# RGBW_DirectControl_Eagle650.net
KiCad netlist of a schematic drawn in EAGLE
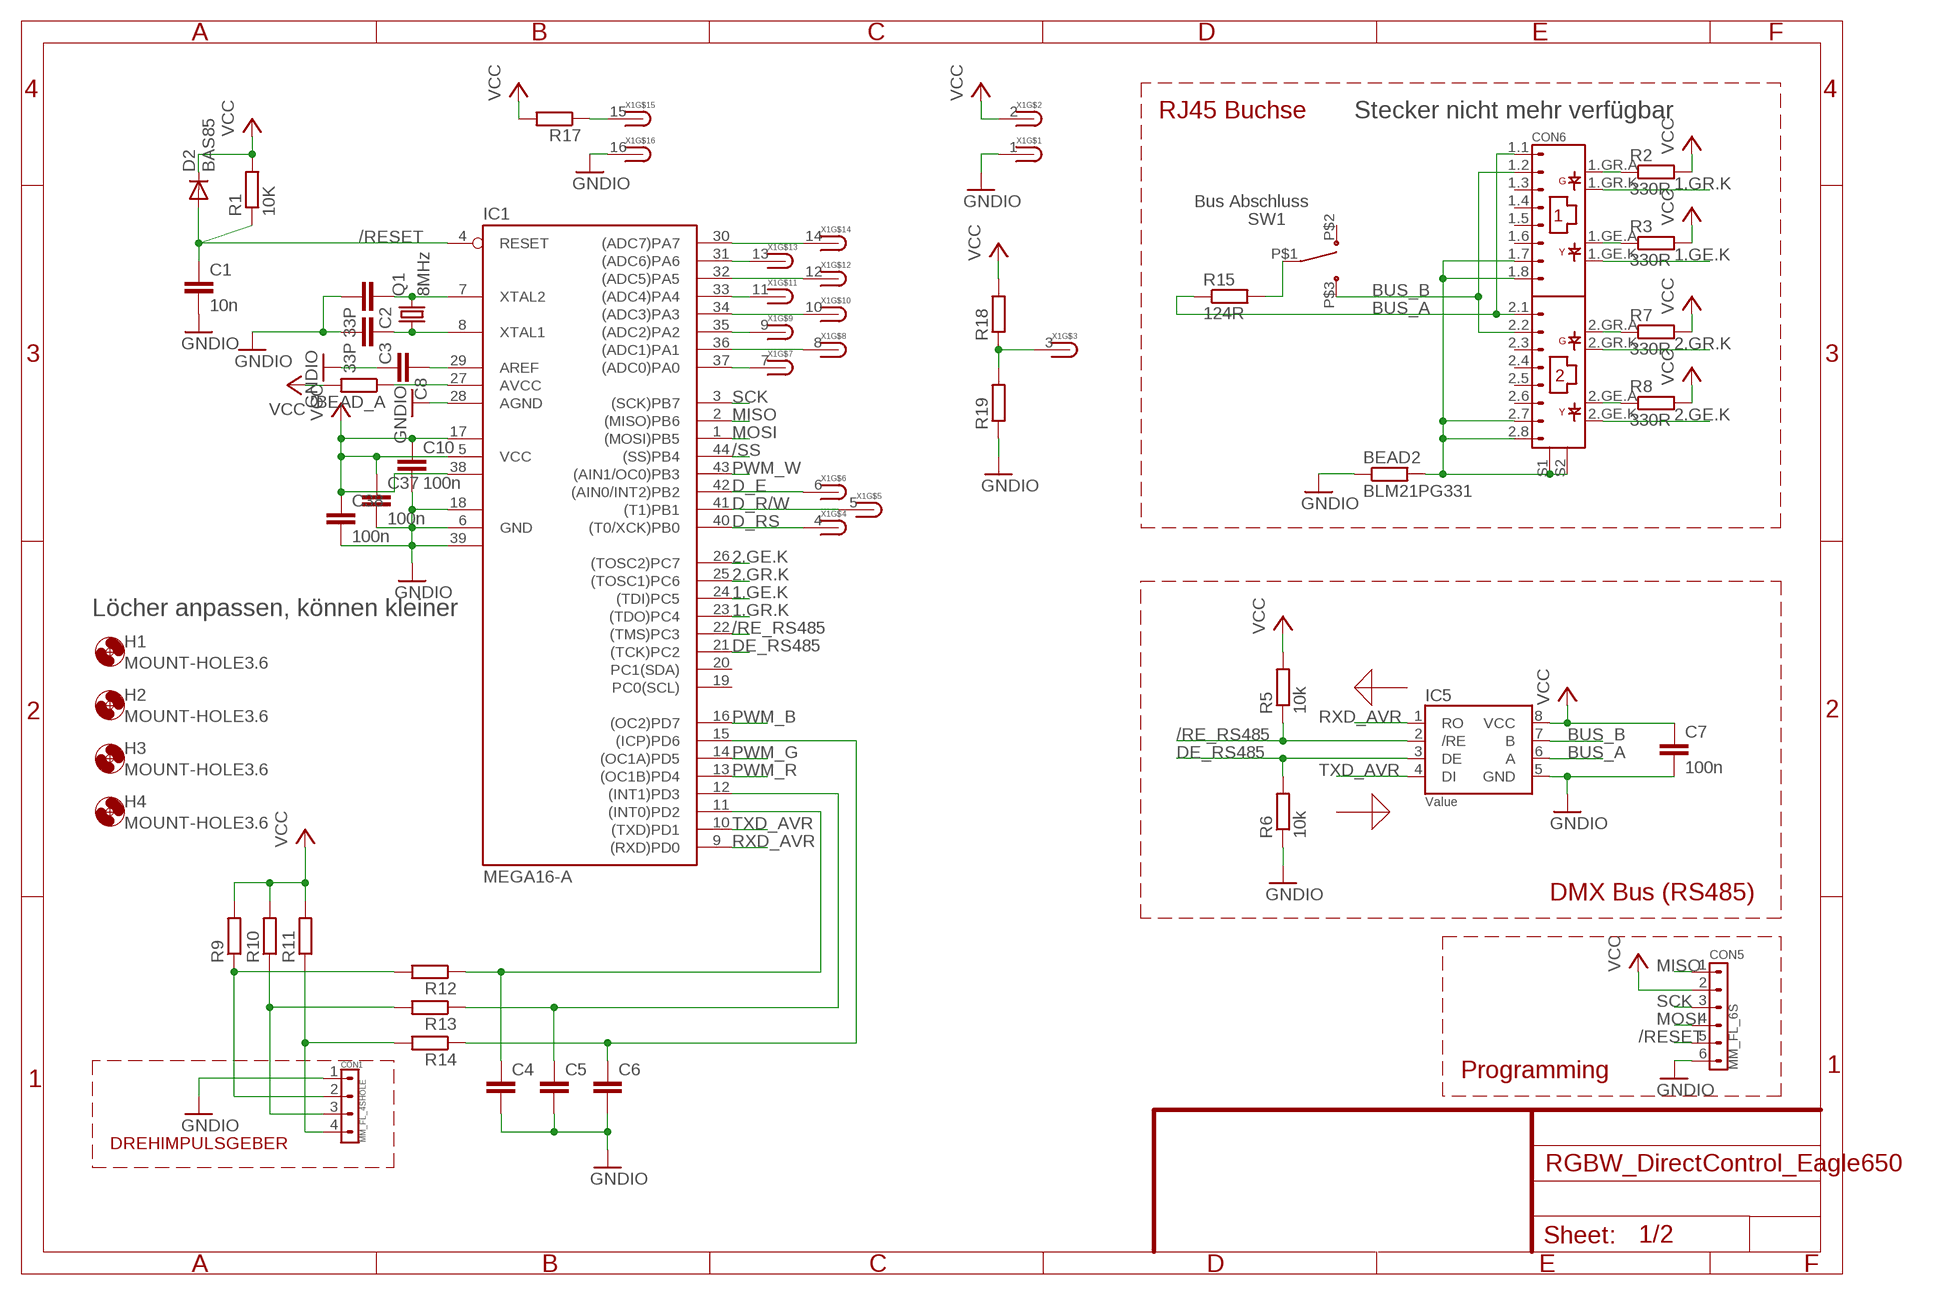
[diagram p0: schematic, sheet 1]
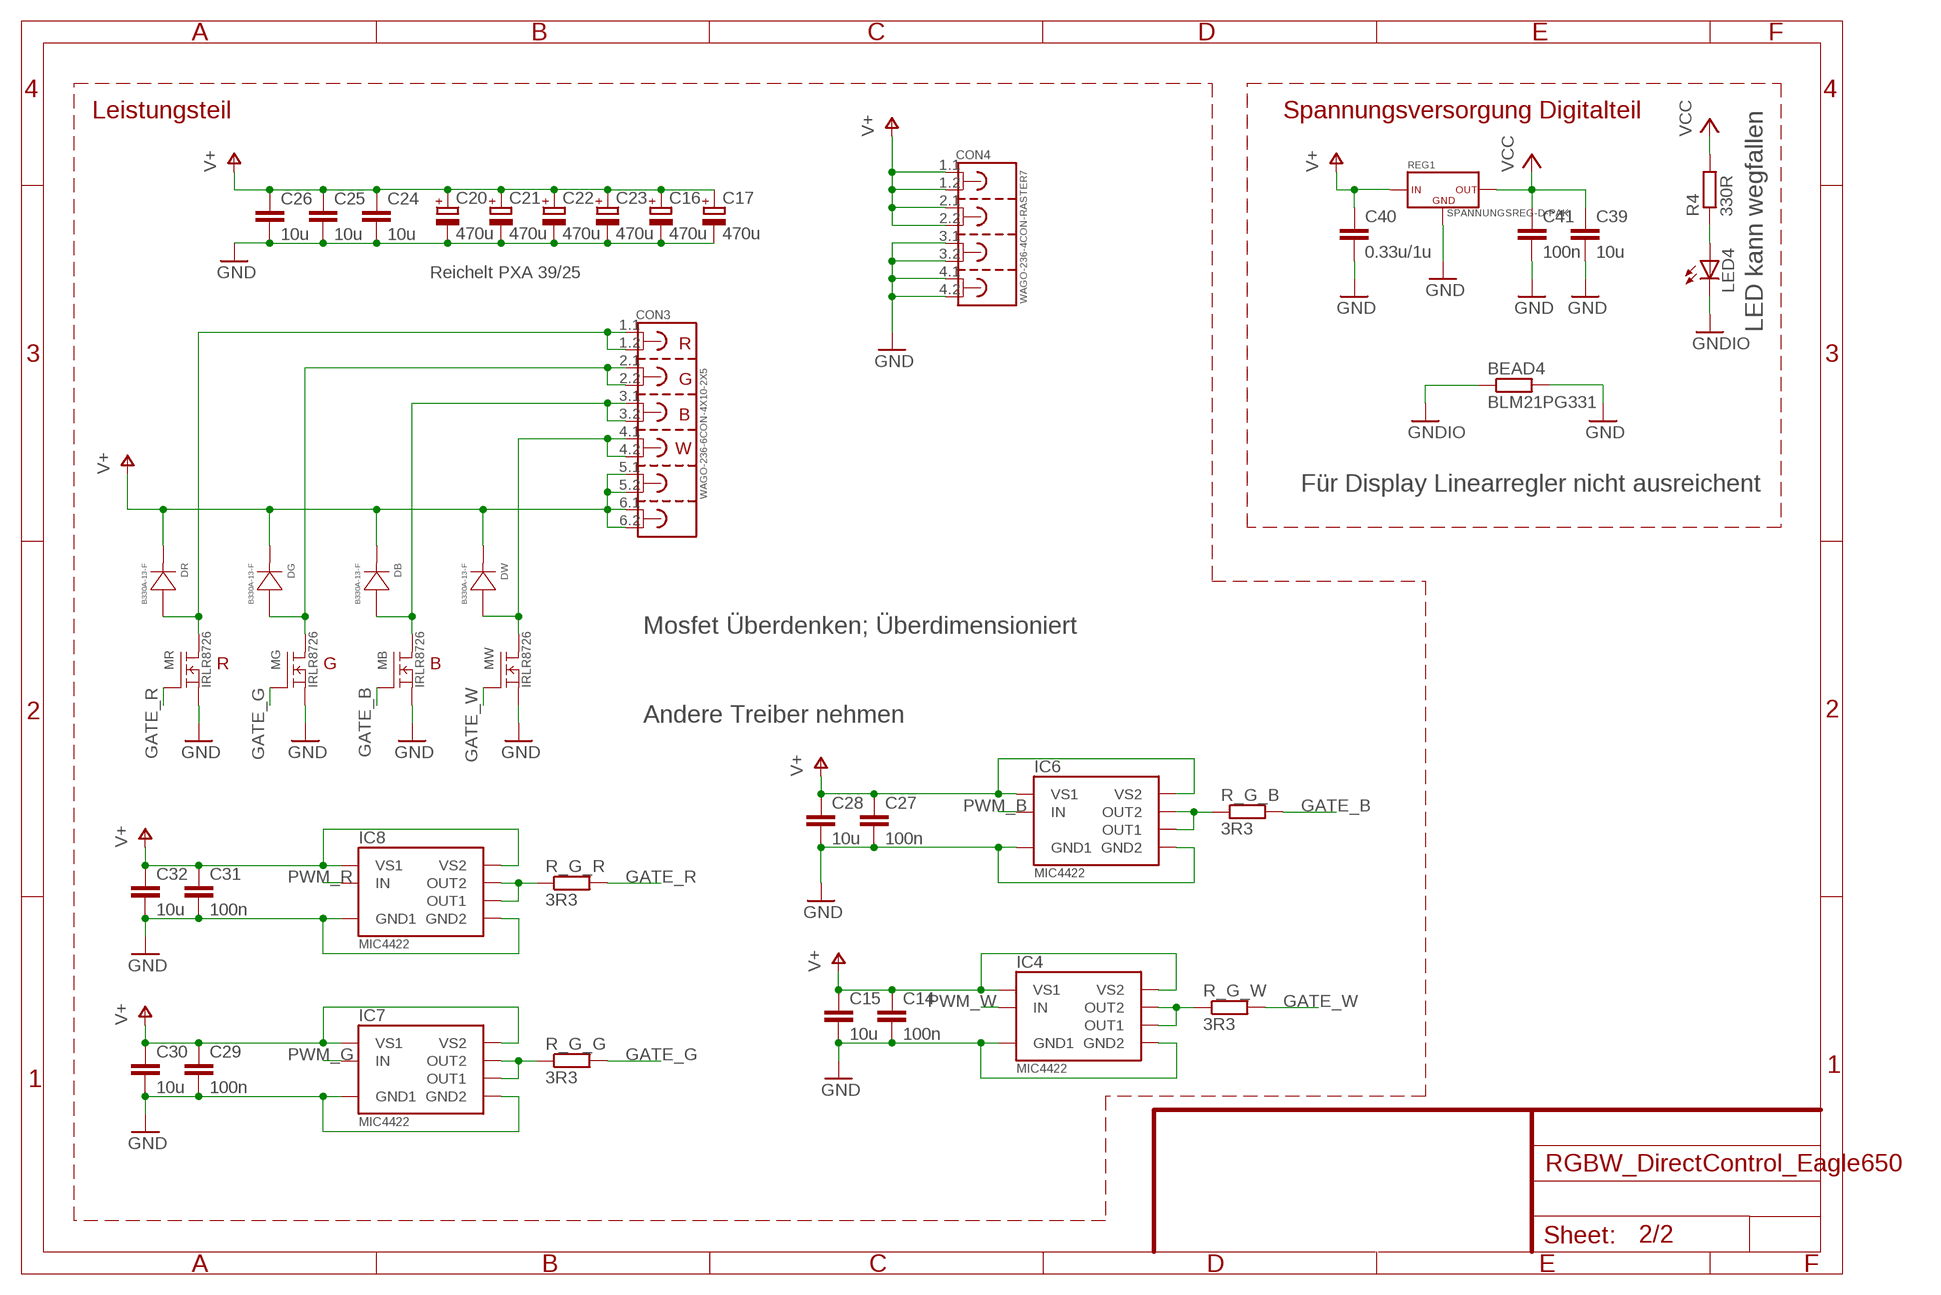
[diagram p1: schematic, sheet 2]

(export (version "E")
  (design (tool "Eeschema 10.0.6"))
  (components
    (comp (ref "BEAD4")
      (value "BLM21PG331")
      (footprint "eagle-import:R0805")
      (libsource (lib "eagle-import") (part "R-EU_R0805"))
    )
    (comp (ref "C14")
      (value "100n")
      (footprint "eagle-import:C0805")
      (libsource (lib "eagle-import") (part "C-EUC0805"))
    )
    (comp (ref "C15")
      (value "10u")
      (footprint "eagle-import:C0805")
      (libsource (lib "eagle-import") (part "C-EUC0805"))
    )
    (comp (ref "C16")
      (value "470u")
      (footprint "eagle-import:E5-10,5")
      (libsource (lib "eagle-import") (part "CPOL-EUE5-10.5"))
    )
    (comp (ref "C17")
      (value "470u")
      (footprint "eagle-import:E5-10,5")
      (libsource (lib "eagle-import") (part "CPOL-EUE5-10.5"))
    )
    (comp (ref "C20")
      (value "470u")
      (footprint "eagle-import:E5-10,5")
      (libsource (lib "eagle-import") (part "CPOL-EUE5-10.5"))
    )
    (comp (ref "C21")
      (value "470u")
      (footprint "eagle-import:E5-10,5")
      (libsource (lib "eagle-import") (part "CPOL-EUE5-10.5"))
    )
    (comp (ref "C22")
      (value "470u")
      (footprint "eagle-import:E5-10,5")
      (libsource (lib "eagle-import") (part "CPOL-EUE5-10.5"))
    )
    (comp (ref "C23")
      (value "470u")
      (footprint "eagle-import:E5-10,5")
      (libsource (lib "eagle-import") (part "CPOL-EUE5-10.5"))
    )
    (comp (ref "C24")
      (value "10u")
      (footprint "eagle-import:C0805")
      (libsource (lib "eagle-import") (part "C-EUC0805"))
    )
    (comp (ref "C25")
      (value "10u")
      (footprint "eagle-import:C0805")
      (libsource (lib "eagle-import") (part "C-EUC0805"))
    )
    (comp (ref "C26")
      (value "10u")
      (footprint "eagle-import:C0805")
      (libsource (lib "eagle-import") (part "C-EUC0805"))
    )
    (comp (ref "C27")
      (value "100n")
      (footprint "eagle-import:C0805")
      (libsource (lib "eagle-import") (part "C-EUC0805"))
    )
    (comp (ref "C28")
      (value "10u")
      (footprint "eagle-import:C0805")
      (libsource (lib "eagle-import") (part "C-EUC0805"))
    )
    (comp (ref "C29")
      (value "100n")
      (footprint "eagle-import:C0805")
      (libsource (lib "eagle-import") (part "C-EUC0805"))
    )
    (comp (ref "C30")
      (value "10u")
      (footprint "eagle-import:C0805")
      (libsource (lib "eagle-import") (part "C-EUC0805"))
    )
    (comp (ref "C31")
      (value "100n")
      (footprint "eagle-import:C0805")
      (libsource (lib "eagle-import") (part "C-EUC0805"))
    )
    (comp (ref "C32")
      (value "10u")
      (footprint "eagle-import:C0805")
      (libsource (lib "eagle-import") (part "C-EUC0805"))
    )
    (comp (ref "C39")
      (value "10u")
      (footprint "eagle-import:C0805")
      (libsource (lib "eagle-import") (part "C-EUC0805"))
    )
    (comp (ref "C40")
      (value "0.33u/1u")
      (footprint "eagle-import:C0805")
      (libsource (lib "eagle-import") (part "C-EUC0805"))
    )
    (comp (ref "C41")
      (value "100n")
      (footprint "eagle-import:C0805")
      (libsource (lib "eagle-import") (part "C-EUC0805"))
    )
    (comp (ref "CON3")
      (value "WAGO-236-6CON-4X10-2X5")
      (footprint "eagle-import:WAGO236_2X5_4X10")
      (libsource (lib "eagle-import") (part "WAGO-236-6CON-4X10-2X5"))
    )
    (comp (ref "CON4")
      (value "WAGO-236-4CON-RASTER7")
      (footprint "eagle-import:WAGO236_7.5_4")
      (libsource (lib "eagle-import") (part "WAGO-236-4CON-RASTER7"))
    )
    (comp (ref "DB")
      (value "B330A-13-F")
      (footprint "eagle-import:SMA")
      (libsource (lib "eagle-import") (part "B330A-13-F"))
    )
    (comp (ref "DG")
      (value "B330A-13-F")
      (footprint "eagle-import:SMA")
      (libsource (lib "eagle-import") (part "B330A-13-F"))
    )
    (comp (ref "DR")
      (value "B330A-13-F")
      (footprint "eagle-import:SMA")
      (libsource (lib "eagle-import") (part "B330A-13-F"))
    )
    (comp (ref "DW")
      (value "B330A-13-F")
      (footprint "eagle-import:SMA")
      (libsource (lib "eagle-import") (part "B330A-13-F"))
    )
    (comp (ref "IC4")
      (value "MIC4422")
      (footprint "eagle-import:SO08")
      (libsource (lib "eagle-import") (part "MIC4422"))
    )
    (comp (ref "IC6")
      (value "MIC4422")
      (footprint "eagle-import:SO08")
      (libsource (lib "eagle-import") (part "MIC4422"))
    )
    (comp (ref "IC7")
      (value "MIC4422")
      (footprint "eagle-import:SO08")
      (libsource (lib "eagle-import") (part "MIC4422"))
    )
    (comp (ref "IC8")
      (value "MIC4422")
      (footprint "eagle-import:SO08")
      (libsource (lib "eagle-import") (part "MIC4422"))
    )
    (comp (ref "LED4")
      (value "LEDCHIP-LED0805")
      (footprint "eagle-import:CHIP-LED0805")
      (libsource (lib "eagle-import") (part "LEDCHIP-LED0805"))
    )
    (comp (ref "MB")
      (value "IRLR8726")
      (footprint "eagle-import:D-PAK")
      (libsource (lib "eagle-import") (part "IRLR8726"))
    )
    (comp (ref "MG")
      (value "IRLR8726")
      (footprint "eagle-import:D-PAK")
      (libsource (lib "eagle-import") (part "IRLR8726"))
    )
    (comp (ref "MR")
      (value "IRLR8726")
      (footprint "eagle-import:D-PAK")
      (libsource (lib "eagle-import") (part "IRLR8726"))
    )
    (comp (ref "MW")
      (value "IRLR8726")
      (footprint "eagle-import:D-PAK")
      (libsource (lib "eagle-import") (part "IRLR8726"))
    )
    (comp (ref "R4")
      (value "330R")
      (footprint "eagle-import:R0805")
      (libsource (lib "eagle-import") (part "R-EU_R0805"))
    )
    (comp (ref "REG1")
      (value "SPANNUNGSREG-D-PAK")
      (footprint "eagle-import:D-PAK")
      (libsource (lib "eagle-import") (part "SPANNUNGSREG-D-PAK"))
    )
    (comp (ref "R_G_B")
      (value "3R3")
      (footprint "eagle-import:R0805")
      (libsource (lib "eagle-import") (part "R-EU_R0805"))
    )
    (comp (ref "R_G_G")
      (value "3R3")
      (footprint "eagle-import:R0805")
      (libsource (lib "eagle-import") (part "R-EU_R0805"))
    )
    (comp (ref "R_G_R")
      (value "3R3")
      (footprint "eagle-import:R0805")
      (libsource (lib "eagle-import") (part "R-EU_R0805"))
    )
    (comp (ref "R_G_W")
      (value "3R3")
      (footprint "eagle-import:R0805")
      (libsource (lib "eagle-import") (part "R-EU_R0805"))
    )
    (comp (ref "BEAD2")
      (value "BLM21PG331")
      (footprint "eagle-import:R0805")
      (libsource (lib "eagle-import") (part "R-EU_R0805"))
    )
    (comp (ref "BEAD_A")
      (value "R-EU_R0805")
      (footprint "eagle-import:R0805")
      (libsource (lib "eagle-import") (part "R-EU_R0805"))
    )
    (comp (ref "C1")
      (value "10n")
      (footprint "eagle-import:C0805")
      (libsource (lib "eagle-import") (part "C-EUC0805"))
    )
    (comp (ref "C2")
      (value "33P")
      (footprint "eagle-import:C0805")
      (libsource (lib "eagle-import") (part "C-EUC0805"))
    )
    (comp (ref "C3")
      (value "33P")
      (footprint "eagle-import:C0805")
      (libsource (lib "eagle-import") (part "C-EUC0805"))
    )
    (comp (ref "C4")
      (value "C-EUC0805")
      (footprint "eagle-import:C0805")
      (libsource (lib "eagle-import") (part "C-EUC0805"))
    )
    (comp (ref "C5")
      (value "C-EUC0805")
      (footprint "eagle-import:C0805")
      (libsource (lib "eagle-import") (part "C-EUC0805"))
    )
    (comp (ref "C6")
      (value "C-EUC0805")
      (footprint "eagle-import:C0805")
      (libsource (lib "eagle-import") (part "C-EUC0805"))
    )
    (comp (ref "C7")
      (value "100n")
      (footprint "eagle-import:C0805")
      (libsource (lib "eagle-import") (part "C-EUC0805"))
    )
    (comp (ref "C8")
      (value "C-EUC0805")
      (footprint "eagle-import:C0805")
      (libsource (lib "eagle-import") (part "C-EUC0805"))
    )
    (comp (ref "C10")
      (value "100n")
      (footprint "eagle-import:C0805")
      (libsource (lib "eagle-import") (part "C-EUC0805"))
    )
    (comp (ref "C37")
      (value "100n")
      (footprint "eagle-import:C0805")
      (libsource (lib "eagle-import") (part "C-EUC0805"))
    )
    (comp (ref "C38")
      (value "100n")
      (footprint "eagle-import:C0805")
      (libsource (lib "eagle-import") (part "C-EUC0805"))
    )
    (comp (ref "CON1")
      (value "MM_FL_4SHOLE")
      (footprint "eagle-import:MM_FL_4G")
      (libsource (lib "eagle-import") (part "MM_FL_4SHOLE"))
    )
    (comp (ref "CON5")
      (value "MM_FL_6S")
      (footprint "eagle-import:MM_FL_6G")
      (libsource (lib "eagle-import") (part "MM_FL_6STH"))
    )
    (comp (ref "CON6")
      (value "RJ45_2ER_LED")
      (footprint "eagle-import:RJ45_2ER_LED")
      (libsource (lib "eagle-import") (part "RJ45_2ER_LED"))
    )
    (comp (ref "D2")
      (value "BAS85")
      (footprint "eagle-import:SOD80C")
      (libsource (lib "eagle-import") (part "DIODE-SOD80C"))
    )
    (comp (ref "H1")
      (value "MOUNT-HOLE3.6")
      (footprint "eagle-import:3,6")
      (libsource (lib "eagle-import") (part "MOUNT-HOLE3.6"))
    )
    (comp (ref "H2")
      (value "MOUNT-HOLE3.6")
      (footprint "eagle-import:3,6")
      (libsource (lib "eagle-import") (part "MOUNT-HOLE3.6"))
    )
    (comp (ref "H3")
      (value "MOUNT-HOLE3.6")
      (footprint "eagle-import:3,6")
      (libsource (lib "eagle-import") (part "MOUNT-HOLE3.6"))
    )
    (comp (ref "H4")
      (value "MOUNT-HOLE3.6")
      (footprint "eagle-import:3,6")
      (libsource (lib "eagle-import") (part "MOUNT-HOLE3.6"))
    )
    (comp (ref "IC1")
      (value "MEGA16-A")
      (footprint "eagle-import:TQFP44")
      (libsource (lib "eagle-import") (part "MEGA16-A"))
    )
    (comp (ref "IC5")
      (value "LT1785")
      (footprint "eagle-import:SO08")
      (libsource (lib "eagle-import") (part "LT1785"))
    )
    (comp (ref "Q1")
      (value "8MHz")
      (footprint "eagle-import:HC49_S")
      (libsource (lib "eagle-import") (part "CRYTALHC49S"))
    )
    (comp (ref "R1")
      (value "10K")
      (footprint "eagle-import:R0805")
      (libsource (lib "eagle-import") (part "R-EU_R0805"))
    )
    (comp (ref "R2")
      (value "330R")
      (footprint "eagle-import:R0805")
      (libsource (lib "eagle-import") (part "R-EU_R0805"))
    )
    (comp (ref "R3")
      (value "330R")
      (footprint "eagle-import:R0805")
      (libsource (lib "eagle-import") (part "R-EU_R0805"))
    )
    (comp (ref "R5")
      (value "10k")
      (footprint "eagle-import:R0805")
      (libsource (lib "eagle-import") (part "R-EU_R0805"))
    )
    (comp (ref "R6")
      (value "10k")
      (footprint "eagle-import:R0805")
      (libsource (lib "eagle-import") (part "R-EU_R0805"))
    )
    (comp (ref "R7")
      (value "330R")
      (footprint "eagle-import:R0805")
      (libsource (lib "eagle-import") (part "R-EU_R0805"))
    )
    (comp (ref "R8")
      (value "330R")
      (footprint "eagle-import:R0805")
      (libsource (lib "eagle-import") (part "R-EU_R0805"))
    )
    (comp (ref "R9")
      (value "R-EU_R0603")
      (footprint "eagle-import:R0603")
      (libsource (lib "eagle-import") (part "R-EU_R0603"))
    )
    (comp (ref "R10")
      (value "R-EU_R0603")
      (footprint "eagle-import:R0603")
      (libsource (lib "eagle-import") (part "R-EU_R0603"))
    )
    (comp (ref "R11")
      (value "R-EU_R0603")
      (footprint "eagle-import:R0603")
      (libsource (lib "eagle-import") (part "R-EU_R0603"))
    )
    (comp (ref "R12")
      (value "R-EU_R0603")
      (footprint "eagle-import:R0603")
      (libsource (lib "eagle-import") (part "R-EU_R0603"))
    )
    (comp (ref "R13")
      (value "R-EU_R0603")
      (footprint "eagle-import:R0603")
      (libsource (lib "eagle-import") (part "R-EU_R0603"))
    )
    (comp (ref "R14")
      (value "R-EU_R0603")
      (footprint "eagle-import:R0603")
      (libsource (lib "eagle-import") (part "R-EU_R0603"))
    )
    (comp (ref "R15")
      (value "124R")
      (footprint "eagle-import:R0805")
      (libsource (lib "eagle-import") (part "R-EU_R0805"))
    )
    (comp (ref "R17")
      (value "R-EU_R0805")
      (footprint "eagle-import:R0805")
      (libsource (lib "eagle-import") (part "R-EU_R0805"))
    )
    (comp (ref "R18")
      (value "R-EU_R0603")
      (footprint "eagle-import:R0603")
      (libsource (lib "eagle-import") (part "R-EU_R0603"))
    )
    (comp (ref "R19")
      (value "R-EU_R0603")
      (footprint "eagle-import:R0603")
      (libsource (lib "eagle-import") (part "R-EU_R0603"))
    )
    (comp (ref "SW1")
      (value "SWITCH_NK236")
      (footprint "eagle-import:SWITCH_NK236")
      (libsource (lib "eagle-import") (part "SWITCH_NK236"))
    )
    (comp (ref "X1")
      (value "MM_FL_16GTH")
      (footprint "eagle-import:MM_FL16G")
      (libsource (lib "eagle-import") (part "MM_FL_16GTH"))
    )
  )
  (nets
    (net (code "1") (name "1.GE.K") (class "Default")
      (node (ref "CON6") (pin "1.GE.K") (pinfunction "1.GE.K_1.GE.K") (pintype "bidirectional"))
      (node (ref "IC1") (pin "24") (pinfunction "(TDI)PC5_24") (pintype "bidirectional"))
    )
    (net (code "2") (name "1.GR.K") (class "Default")
      (node (ref "CON6") (pin "1.GR.K") (pinfunction "1.GR.K_1.GR.K") (pintype "bidirectional"))
      (node (ref "IC1") (pin "23") (pinfunction "(TDO)PC4_23") (pintype "bidirectional"))
    )
    (net (code "3") (name "2.GE.K") (class "Default")
      (node (ref "CON6") (pin "2.GE.K") (pinfunction "2.GE.K_2.GE.K") (pintype "bidirectional"))
      (node (ref "IC1") (pin "26") (pinfunction "(TOSC2)PC7_26") (pintype "bidirectional"))
    )
    (net (code "4") (name "2.GR.K") (class "Default")
      (node (ref "CON6") (pin "2.GR.K") (pinfunction "2.GR.K_2.GR.K") (pintype "bidirectional"))
      (node (ref "IC1") (pin "25") (pinfunction "(TOSC1)PC6_25") (pintype "bidirectional"))
    )
    (net (code "5") (name "BUS_A") (class "Default")
      (node (ref "CON6") (pin "1.1") (pinfunction "1.1_1.1") (pintype "bidirectional"))
      (node (ref "CON6") (pin "2.1") (pinfunction "2.1_2.1") (pintype "bidirectional"))
      (node (ref "IC5") (pin "6") (pinfunction "A_6") (pintype "bidirectional"))
      (node (ref "R15") (pin "1") (pinfunction "1_1") (pintype "passive"))
    )
    (net (code "6") (name "BUS_B") (class "Default")
      (node (ref "CON6") (pin "1.2") (pinfunction "1.2_1.2") (pintype "bidirectional"))
      (node (ref "CON6") (pin "2.2") (pinfunction "2.2_2.2") (pintype "bidirectional"))
      (node (ref "IC5") (pin "7") (pinfunction "B_7") (pintype "bidirectional"))
      (node (ref "SW1") (pin "P$3") (pinfunction "3_P$3") (pintype "bidirectional"))
    )
    (net (code "7") (name "DE_RS485") (class "Default")
      (node (ref "IC1") (pin "21") (pinfunction "(TCK)PC2_21") (pintype "bidirectional"))
      (node (ref "IC5") (pin "3") (pinfunction "DE_3") (pintype "bidirectional"))
      (node (ref "R6") (pin "2") (pinfunction "2_2") (pintype "passive"))
    )
    (net (code "8") (name "D_E") (class "Default")
      (node (ref "IC1") (pin "42") (pinfunction "(AIN0/INT2)PB2_42") (pintype "bidirectional"))
      (node (ref "X1") (pin "6") (pinfunction "P$1_6") (pintype "bidirectional"))
    )
    (net (code "9") (name "D_RS") (class "Default")
      (node (ref "IC1") (pin "40") (pinfunction "(T0/XCK)PB0_40") (pintype "bidirectional"))
      (node (ref "X1") (pin "4") (pinfunction "P$1_4") (pintype "bidirectional"))
    )
    (net (code "10") (name "D_R{slash}W") (class "Default")
      (node (ref "IC1") (pin "41") (pinfunction "(T1)PB1_41") (pintype "bidirectional"))
      (node (ref "X1") (pin "5") (pinfunction "P$1_5") (pintype "bidirectional"))
    )
    (net (code "11") (name "GATE_B") (class "Default")
      (node (ref "MB") (pin "G") (pinfunction "G_G") (pintype "bidirectional"))
      (node (ref "R_G_B") (pin "2") (pinfunction "2_2") (pintype "passive"))
    )
    (net (code "12") (name "GATE_G") (class "Default")
      (node (ref "MG") (pin "G") (pinfunction "G_G") (pintype "bidirectional"))
      (node (ref "R_G_G") (pin "2") (pinfunction "2_2") (pintype "passive"))
    )
    (net (code "13") (name "GATE_R") (class "Default")
      (node (ref "MR") (pin "G") (pinfunction "G_G") (pintype "bidirectional"))
      (node (ref "R_G_R") (pin "2") (pinfunction "2_2") (pintype "passive"))
    )
    (net (code "14") (name "GATE_W") (class "Default")
      (node (ref "MW") (pin "G") (pinfunction "G_G") (pintype "bidirectional"))
      (node (ref "R_G_W") (pin "2") (pinfunction "2_2") (pintype "passive"))
    )
    (net (code "15") (name "GND") (class "Default")
      (node (ref "BEAD4") (pin "2") (pinfunction "2_2") (pintype "passive"))
      (node (ref "C14") (pin "2") (pinfunction "2_2") (pintype "passive"))
      (node (ref "C15") (pin "2") (pinfunction "2_2") (pintype "passive"))
      (node (ref "C16") (pin "-") (pinfunction "-_-") (pintype "passive"))
      (node (ref "C17") (pin "-") (pinfunction "-_-") (pintype "passive"))
      (node (ref "C20") (pin "-") (pinfunction "-_-") (pintype "passive"))
      (node (ref "C21") (pin "-") (pinfunction "-_-") (pintype "passive"))
      (node (ref "C22") (pin "-") (pinfunction "-_-") (pintype "passive"))
      (node (ref "C23") (pin "-") (pinfunction "-_-") (pintype "passive"))
      (node (ref "C24") (pin "2") (pinfunction "2_2") (pintype "passive"))
      (node (ref "C25") (pin "2") (pinfunction "2_2") (pintype "passive"))
      (node (ref "C26") (pin "2") (pinfunction "2_2") (pintype "passive"))
      (node (ref "C27") (pin "2") (pinfunction "2_2") (pintype "passive"))
      (node (ref "C28") (pin "2") (pinfunction "2_2") (pintype "passive"))
      (node (ref "C29") (pin "2") (pinfunction "2_2") (pintype "passive"))
      (node (ref "C30") (pin "2") (pinfunction "2_2") (pintype "passive"))
      (node (ref "C31") (pin "2") (pinfunction "2_2") (pintype "passive"))
      (node (ref "C32") (pin "2") (pinfunction "2_2") (pintype "passive"))
      (node (ref "C39") (pin "2") (pinfunction "2_2") (pintype "passive"))
      (node (ref "C40") (pin "2") (pinfunction "2_2") (pintype "passive"))
      (node (ref "C41") (pin "2") (pinfunction "2_2") (pintype "passive"))
      (node (ref "CON4") (pin "3.1") (pinfunction "P$5_3.1") (pintype "bidirectional"))
      (node (ref "CON4") (pin "3.2") (pinfunction "P$6_3.2") (pintype "bidirectional"))
      (node (ref "CON4") (pin "4.1") (pinfunction "P$7_4.1") (pintype "bidirectional"))
      (node (ref "CON4") (pin "4.2") (pinfunction "P$8_4.2") (pintype "bidirectional"))
      (node (ref "IC4") (pin "4") (pinfunction "GND1_4") (pintype "bidirectional"))
      (node (ref "IC4") (pin "5") (pinfunction "GND2_5") (pintype "bidirectional"))
      (node (ref "IC6") (pin "4") (pinfunction "GND1_4") (pintype "bidirectional"))
      (node (ref "IC6") (pin "5") (pinfunction "GND2_5") (pintype "bidirectional"))
      (node (ref "IC7") (pin "4") (pinfunction "GND1_4") (pintype "bidirectional"))
      (node (ref "IC7") (pin "5") (pinfunction "GND2_5") (pintype "bidirectional"))
      (node (ref "IC8") (pin "4") (pinfunction "GND1_4") (pintype "bidirectional"))
      (node (ref "IC8") (pin "5") (pinfunction "GND2_5") (pintype "bidirectional"))
      (node (ref "MB") (pin "S") (pinfunction "S_S") (pintype "bidirectional"))
      (node (ref "MG") (pin "S") (pinfunction "S_S") (pintype "bidirectional"))
      (node (ref "MR") (pin "S") (pinfunction "S_S") (pintype "bidirectional"))
      (node (ref "MW") (pin "S") (pinfunction "S_S") (pintype "bidirectional"))
      (node (ref "REG1") (pin "D") (pinfunction "GND_D") (pintype "bidirectional"))
    )
    (net (code "16") (name "GNDIO") (class "Default")
      (node (ref "BEAD2") (pin "1") (pinfunction "1_1") (pintype "passive"))
      (node (ref "BEAD4") (pin "1") (pinfunction "1_1") (pintype "passive"))
      (node (ref "C1") (pin "2") (pinfunction "2_2") (pintype "passive"))
      (node (ref "C10") (pin "2") (pinfunction "2_2") (pintype "passive"))
      (node (ref "C2") (pin "2") (pinfunction "2_2") (pintype "passive"))
      (node (ref "C3") (pin "2") (pinfunction "2_2") (pintype "passive"))
      (node (ref "C37") (pin "2") (pinfunction "2_2") (pintype "passive"))
      (node (ref "C38") (pin "2") (pinfunction "2_2") (pintype "passive"))
      (node (ref "C4") (pin "2") (pinfunction "2_2") (pintype "passive"))
      (node (ref "C5") (pin "2") (pinfunction "2_2") (pintype "passive"))
      (node (ref "C6") (pin "2") (pinfunction "2_2") (pintype "passive"))
      (node (ref "C7") (pin "2") (pinfunction "2_2") (pintype "passive"))
      (node (ref "C8") (pin "2") (pinfunction "2_2") (pintype "passive"))
      (node (ref "CON1") (pin "1") (pinfunction "P$1_1") (pintype "bidirectional"))
      (node (ref "CON5") (pin "6") (pinfunction "P$6_6") (pintype "bidirectional"))
      (node (ref "IC1") (pin "18") (pinfunction "GND1_18") (pintype "power_in"))
      (node (ref "IC1") (pin "28") (pinfunction "AGND_28") (pintype "power_in"))
      (node (ref "IC1") (pin "39") (pinfunction "GND2_39") (pintype "power_in"))
      (node (ref "IC1") (pin "6") (pinfunction "GND_6") (pintype "power_in"))
      (node (ref "IC5") (pin "5") (pinfunction "GND_5") (pintype "bidirectional"))
      (node (ref "LED4") (pin "C") (pinfunction "C_C") (pintype "passive"))
      (node (ref "R19") (pin "1") (pinfunction "1_1") (pintype "passive"))
      (node (ref "R6") (pin "1") (pinfunction "1_1") (pintype "passive"))
      (node (ref "X1") (pin "1") (pinfunction "P$1_1") (pintype "bidirectional"))
      (node (ref "X1") (pin "16") (pinfunction "P$1_16") (pintype "bidirectional"))
    )
    (net (code "17") (name "MISO") (class "Default")
      (node (ref "CON5") (pin "1") (pinfunction "P$1_1") (pintype "bidirectional"))
      (node (ref "IC1") (pin "2") (pinfunction "(MISO)PB6_2") (pintype "bidirectional"))
    )
    (net (code "18") (name "MOSI") (class "Default")
      (node (ref "CON5") (pin "4") (pinfunction "P$4_4") (pintype "bidirectional"))
      (node (ref "IC1") (pin "1") (pinfunction "(MOSI)PB5_1") (pintype "bidirectional"))
    )
    (net (code "19") (name "Net-(BEAD2-Pad2)") (class "Default")
      (node (ref "BEAD2") (pin "2") (pinfunction "2_2") (pintype "passive"))
      (node (ref "CON6") (pin "1.7") (pinfunction "1.7_1.7") (pintype "bidirectional"))
      (node (ref "CON6") (pin "1.8") (pinfunction "1.8_1.8") (pintype "bidirectional"))
      (node (ref "CON6") (pin "2.7") (pinfunction "2.7_2.7") (pintype "bidirectional"))
      (node (ref "CON6") (pin "2.8") (pinfunction "2.8_2.8") (pintype "bidirectional"))
      (node (ref "CON6") (pin "S1") (pinfunction "S1_S1") (pintype "bidirectional"))
      (node (ref "CON6") (pin "S2") (pinfunction "S2_S2") (pintype "bidirectional"))
    )
    (net (code "20") (name "Net-(CON1-P$2)") (class "Default")
      (node (ref "CON1") (pin "2") (pinfunction "P$2_2") (pintype "bidirectional"))
      (node (ref "R12") (pin "2") (pinfunction "2_2") (pintype "passive"))
      (node (ref "R9") (pin "1") (pinfunction "1_1") (pintype "passive"))
    )
    (net (code "21") (name "Net-(CON1-P$3)") (class "Default")
      (node (ref "CON1") (pin "3") (pinfunction "P$3_3") (pintype "bidirectional"))
      (node (ref "R10") (pin "1") (pinfunction "1_1") (pintype "passive"))
      (node (ref "R13") (pin "2") (pinfunction "2_2") (pintype "passive"))
    )
    (net (code "22") (name "Net-(CON1-P$4)") (class "Default")
      (node (ref "CON1") (pin "4") (pinfunction "P$4_4") (pintype "bidirectional"))
      (node (ref "R11") (pin "1") (pinfunction "1_1") (pintype "passive"))
      (node (ref "R14") (pin "2") (pinfunction "2_2") (pintype "passive"))
    )
    (net (code "23") (name "Net-(CON3-3.3)") (class "Default")
      (node (ref "CON3") (pin "3.1") (pinfunction "3.1_3.1") (pintype "bidirectional"))
      (node (ref "CON3") (pin "3.2") (pinfunction "3.3_3.2") (pintype "bidirectional"))
      (node (ref "DB") (pin "A") (pinfunction "A_A") (pintype "bidirectional"))
      (node (ref "MB") (pin "D") (pinfunction "D_D") (pintype "bidirectional"))
    )
    (net (code "24") (name "Net-(CON3-Pad1.1)") (class "Default")
      (node (ref "CON3") (pin "1.1") (pinfunction "1.1_1.1") (pintype "bidirectional"))
      (node (ref "CON3") (pin "1.2") (pinfunction "1.2_1.2") (pintype "bidirectional"))
      (node (ref "DR") (pin "A") (pinfunction "A_A") (pintype "bidirectional"))
      (node (ref "MR") (pin "D") (pinfunction "D_D") (pintype "bidirectional"))
    )
    (net (code "25") (name "Net-(CON3-Pad2.1)") (class "Default")
      (node (ref "CON3") (pin "2.1") (pinfunction "2.1_2.1") (pintype "bidirectional"))
      (node (ref "CON3") (pin "2.2") (pinfunction "2.2_2.2") (pintype "bidirectional"))
      (node (ref "DG") (pin "A") (pinfunction "A_A") (pintype "bidirectional"))
      (node (ref "MG") (pin "D") (pinfunction "D_D") (pintype "bidirectional"))
    )
    (net (code "26") (name "Net-(CON3-Pad4.1)") (class "Default")
      (node (ref "CON3") (pin "4.1") (pinfunction "4.1_4.1") (pintype "bidirectional"))
      (node (ref "CON3") (pin "4.2") (pinfunction "4.2_4.2") (pintype "bidirectional"))
      (node (ref "DW") (pin "A") (pinfunction "A_A") (pintype "bidirectional"))
      (node (ref "MW") (pin "D") (pinfunction "D_D") (pintype "bidirectional"))
    )
    (net (code "27") (name "Net-(CON6-Pad1.GE.A)") (class "Default")
      (node (ref "CON6") (pin "1.GE.A") (pinfunction "1.GE.A_1.GE.A") (pintype "bidirectional"))
      (node (ref "R3") (pin "1") (pinfunction "1_1") (pintype "passive"))
    )
    (net (code "28") (name "Net-(CON6-Pad1.GR.A)") (class "Default")
      (node (ref "CON6") (pin "1.GR.A") (pinfunction "1.GR.A_1.GR.A") (pintype "bidirectional"))
      (node (ref "R2") (pin "1") (pinfunction "1_1") (pintype "passive"))
    )
    (net (code "29") (name "Net-(CON6-Pad2.GE.A)") (class "Default")
      (node (ref "CON6") (pin "2.GE.A") (pinfunction "2.GE.A_2.GE.A") (pintype "bidirectional"))
      (node (ref "R8") (pin "1") (pinfunction "1_1") (pintype "passive"))
    )
    (net (code "30") (name "Net-(CON6-Pad2.GR.A)") (class "Default")
      (node (ref "CON6") (pin "2.GR.A") (pinfunction "2.GR.A_2.GR.A") (pintype "bidirectional"))
      (node (ref "R7") (pin "1") (pinfunction "1_1") (pintype "passive"))
    )
    (net (code "31") (name "Net-(IC1-(ADC0)PA0)") (class "Default")
      (node (ref "IC1") (pin "37") (pinfunction "(ADC0)PA0_37") (pintype "bidirectional"))
      (node (ref "X1") (pin "7") (pinfunction "P$1_7") (pintype "bidirectional"))
    )
    (net (code "32") (name "Net-(IC1-(ADC1)PA1)") (class "Default")
      (node (ref "IC1") (pin "36") (pinfunction "(ADC1)PA1_36") (pintype "bidirectional"))
      (node (ref "X1") (pin "8") (pinfunction "P$1_8") (pintype "bidirectional"))
    )
    (net (code "33") (name "Net-(IC1-(ADC2)PA2)") (class "Default")
      (node (ref "IC1") (pin "35") (pinfunction "(ADC2)PA2_35") (pintype "bidirectional"))
      (node (ref "X1") (pin "9") (pinfunction "P$1_9") (pintype "bidirectional"))
    )
    (net (code "34") (name "Net-(IC1-(ADC3)PA3)") (class "Default")
      (node (ref "IC1") (pin "34") (pinfunction "(ADC3)PA3_34") (pintype "bidirectional"))
      (node (ref "X1") (pin "10") (pinfunction "P$1_10") (pintype "bidirectional"))
    )
    (net (code "35") (name "Net-(IC1-(ADC4)PA4)") (class "Default")
      (node (ref "IC1") (pin "33") (pinfunction "(ADC4)PA4_33") (pintype "bidirectional"))
      (node (ref "X1") (pin "11") (pinfunction "P$1_11") (pintype "bidirectional"))
    )
    (net (code "36") (name "Net-(IC1-(ADC5)PA5)") (class "Default")
      (node (ref "IC1") (pin "32") (pinfunction "(ADC5)PA5_32") (pintype "bidirectional"))
      (node (ref "X1") (pin "12") (pinfunction "P$1_12") (pintype "bidirectional"))
    )
    (net (code "37") (name "Net-(IC1-(ADC6)PA6)") (class "Default")
      (node (ref "IC1") (pin "31") (pinfunction "(ADC6)PA6_31") (pintype "bidirectional"))
      (node (ref "X1") (pin "13") (pinfunction "P$1_13") (pintype "bidirectional"))
    )
    (net (code "38") (name "Net-(IC1-(ADC7)PA7)") (class "Default")
      (node (ref "IC1") (pin "30") (pinfunction "(ADC7)PA7_30") (pintype "bidirectional"))
      (node (ref "X1") (pin "14") (pinfunction "P$1_14") (pintype "bidirectional"))
    )
    (net (code "39") (name "Net-(IC1-(ICP)PD6)") (class "Default")
      (node (ref "C6") (pin "1") (pinfunction "1_1") (pintype "passive"))
      (node (ref "IC1") (pin "15") (pinfunction "(ICP)PD6_15") (pintype "bidirectional"))
      (node (ref "R14") (pin "1") (pinfunction "1_1") (pintype "passive"))
    )
    (net (code "40") (name "Net-(IC1-(INT0)PD2)") (class "Default")
      (node (ref "C4") (pin "1") (pinfunction "1_1") (pintype "passive"))
      (node (ref "IC1") (pin "11") (pinfunction "(INT0)PD2_11") (pintype "bidirectional"))
      (node (ref "R12") (pin "1") (pinfunction "1_1") (pintype "passive"))
    )
    (net (code "41") (name "Net-(IC1-(INT1)PD3)") (class "Default")
      (node (ref "C5") (pin "1") (pinfunction "1_1") (pintype "passive"))
      (node (ref "IC1") (pin "12") (pinfunction "(INT1)PD3_12") (pintype "bidirectional"))
      (node (ref "R13") (pin "1") (pinfunction "1_1") (pintype "passive"))
    )
    (net (code "42") (name "Net-(IC1-AREF)") (class "Default")
      (node (ref "C8") (pin "1") (pinfunction "1_1") (pintype "passive"))
      (node (ref "IC1") (pin "29") (pinfunction "AREF_29") (pintype "power_in"))
    )
    (net (code "43") (name "Net-(IC1-AVCC)") (class "Default")
      (node (ref "BEAD_A") (pin "1") (pinfunction "1_1") (pintype "passive"))
      (node (ref "IC1") (pin "27") (pinfunction "AVCC_27") (pintype "power_in"))
    )
    (net (code "44") (name "Net-(IC1-XTAL1)") (class "Default")
      (node (ref "C3") (pin "1") (pinfunction "1_1") (pintype "passive"))
      (node (ref "IC1") (pin "8") (pinfunction "XTAL1_8") (pintype "bidirectional"))
      (node (ref "Q1") (pin "1") (pinfunction "1_1") (pintype "passive"))
    )
    (net (code "45") (name "Net-(IC1-XTAL2)") (class "Default")
      (node (ref "C2") (pin "1") (pinfunction "1_1") (pintype "passive"))
      (node (ref "IC1") (pin "7") (pinfunction "XTAL2_7") (pintype "bidirectional"))
      (node (ref "Q1") (pin "2") (pinfunction "2_2") (pintype "passive"))
    )
    (net (code "46") (name "Net-(IC4-OUT1)") (class "Default")
      (node (ref "IC4") (pin "6") (pinfunction "OUT1_6") (pintype "bidirectional"))
      (node (ref "IC4") (pin "7") (pinfunction "OUT2_7") (pintype "bidirectional"))
      (node (ref "R_G_W") (pin "1") (pinfunction "1_1") (pintype "passive"))
    )
    (net (code "47") (name "Net-(IC6-OUT1)") (class "Default")
      (node (ref "IC6") (pin "6") (pinfunction "OUT1_6") (pintype "bidirectional"))
      (node (ref "IC6") (pin "7") (pinfunction "OUT2_7") (pintype "bidirectional"))
      (node (ref "R_G_B") (pin "1") (pinfunction "1_1") (pintype "passive"))
    )
    (net (code "48") (name "Net-(IC7-OUT1)") (class "Default")
      (node (ref "IC7") (pin "6") (pinfunction "OUT1_6") (pintype "bidirectional"))
      (node (ref "IC7") (pin "7") (pinfunction "OUT2_7") (pintype "bidirectional"))
      (node (ref "R_G_G") (pin "1") (pinfunction "1_1") (pintype "passive"))
    )
    (net (code "49") (name "Net-(IC8-OUT1)") (class "Default")
      (node (ref "IC8") (pin "6") (pinfunction "OUT1_6") (pintype "bidirectional"))
      (node (ref "IC8") (pin "7") (pinfunction "OUT2_7") (pintype "bidirectional"))
      (node (ref "R_G_R") (pin "1") (pinfunction "1_1") (pintype "passive"))
    )
    (net (code "50") (name "Net-(LED4-PadA)") (class "Default")
      (node (ref "LED4") (pin "A") (pinfunction "A_A") (pintype "passive"))
      (node (ref "R4") (pin "1") (pinfunction "1_1") (pintype "passive"))
    )
    (net (code "51") (name "Net-(SW1-1)") (class "Default")
      (node (ref "R15") (pin "2") (pinfunction "2_2") (pintype "passive"))
      (node (ref "SW1") (pin "P$1") (pinfunction "1_P$1") (pintype "bidirectional"))
    )
    (net (code "52") (name "Net-(X1G-P$1)") (class "Default")
      (node (ref "R17") (pin "1") (pinfunction "1_1") (pintype "passive"))
      (node (ref "X1") (pin "15") (pinfunction "P$1_15") (pintype "bidirectional"))
    )
    (net (code "53") (name "Net-(X1J-P$1)") (class "Default")
      (node (ref "R18") (pin "1") (pinfunction "1_1") (pintype "passive"))
      (node (ref "R19") (pin "2") (pinfunction "2_2") (pintype "passive"))
      (node (ref "X1") (pin "3") (pinfunction "P$1_3") (pintype "bidirectional"))
    )
    (net (code "54") (name "PWM_B") (class "Default")
      (node (ref "IC1") (pin "16") (pinfunction "(OC2)PD7_16") (pintype "bidirectional"))
      (node (ref "IC6") (pin "2") (pinfunction "IN_2") (pintype "bidirectional"))
    )
    (net (code "55") (name "PWM_G") (class "Default")
      (node (ref "IC1") (pin "14") (pinfunction "(OC1A)PD5_14") (pintype "bidirectional"))
      (node (ref "IC7") (pin "2") (pinfunction "IN_2") (pintype "bidirectional"))
    )
    (net (code "56") (name "PWM_R") (class "Default")
      (node (ref "IC1") (pin "13") (pinfunction "(OC1B)PD4_13") (pintype "bidirectional"))
      (node (ref "IC8") (pin "2") (pinfunction "IN_2") (pintype "bidirectional"))
    )
    (net (code "57") (name "PWM_W") (class "Default")
      (node (ref "IC1") (pin "43") (pinfunction "(AIN1/OC0)PB3_43") (pintype "bidirectional"))
      (node (ref "IC4") (pin "2") (pinfunction "IN_2") (pintype "bidirectional"))
    )
    (net (code "58") (name "RXD_AVR") (class "Default")
      (node (ref "IC1") (pin "9") (pinfunction "(RXD)PD0_9") (pintype "bidirectional"))
      (node (ref "IC5") (pin "1") (pinfunction "RO_1") (pintype "bidirectional"))
    )
    (net (code "59") (name "SCK") (class "Default")
      (node (ref "CON5") (pin "3") (pinfunction "P$3_3") (pintype "bidirectional"))
      (node (ref "IC1") (pin "3") (pinfunction "(SCK)PB7_3") (pintype "bidirectional"))
    )
    (net (code "60") (name "TXD_AVR") (class "Default")
      (node (ref "IC1") (pin "10") (pinfunction "(TXD)PD1_10") (pintype "bidirectional"))
      (node (ref "IC5") (pin "4") (pinfunction "DI_4") (pintype "bidirectional"))
    )
    (net (code "61") (name "V+") (class "Default")
      (node (ref "C14") (pin "1") (pinfunction "1_1") (pintype "passive"))
      (node (ref "C15") (pin "1") (pinfunction "1_1") (pintype "passive"))
      (node (ref "C16") (pin "+") (pinfunction "+_+") (pintype "passive"))
      (node (ref "C17") (pin "+") (pinfunction "+_+") (pintype "passive"))
      (node (ref "C20") (pin "+") (pinfunction "+_+") (pintype "passive"))
      (node (ref "C21") (pin "+") (pinfunction "+_+") (pintype "passive"))
      (node (ref "C22") (pin "+") (pinfunction "+_+") (pintype "passive"))
      (node (ref "C23") (pin "+") (pinfunction "+_+") (pintype "passive"))
      (node (ref "C24") (pin "1") (pinfunction "1_1") (pintype "passive"))
      (node (ref "C25") (pin "1") (pinfunction "1_1") (pintype "passive"))
      (node (ref "C26") (pin "1") (pinfunction "1_1") (pintype "passive"))
      (node (ref "C27") (pin "1") (pinfunction "1_1") (pintype "passive"))
      (node (ref "C28") (pin "1") (pinfunction "1_1") (pintype "passive"))
      (node (ref "C29") (pin "1") (pinfunction "1_1") (pintype "passive"))
      (node (ref "C30") (pin "1") (pinfunction "1_1") (pintype "passive"))
      (node (ref "C31") (pin "1") (pinfunction "1_1") (pintype "passive"))
      (node (ref "C32") (pin "1") (pinfunction "1_1") (pintype "passive"))
      (node (ref "C40") (pin "1") (pinfunction "1_1") (pintype "passive"))
      (node (ref "CON3") (pin "5.1") (pinfunction "5.1_5.1") (pintype "bidirectional"))
      (node (ref "CON3") (pin "5.2") (pinfunction "5.2_5.2") (pintype "bidirectional"))
      (node (ref "CON3") (pin "6.1") (pinfunction "6.1_6.1") (pintype "bidirectional"))
      (node (ref "CON3") (pin "6.2") (pinfunction "6.2_6.2") (pintype "bidirectional"))
      (node (ref "CON4") (pin "1.1") (pinfunction "P$1_1.1") (pintype "bidirectional"))
      (node (ref "CON4") (pin "1.2") (pinfunction "P$2_1.2") (pintype "bidirectional"))
      (node (ref "CON4") (pin "2.1") (pinfunction "P$3_2.1") (pintype "bidirectional"))
      (node (ref "CON4") (pin "2.2") (pinfunction "P$4_2.2") (pintype "bidirectional"))
      (node (ref "DB") (pin "K") (pinfunction "K_K") (pintype "bidirectional"))
      (node (ref "DG") (pin "K") (pinfunction "K_K") (pintype "bidirectional"))
      (node (ref "DR") (pin "K") (pinfunction "K_K") (pintype "bidirectional"))
      (node (ref "DW") (pin "K") (pinfunction "K_K") (pintype "bidirectional"))
      (node (ref "IC4") (pin "1") (pinfunction "VS1_1") (pintype "bidirectional"))
      (node (ref "IC4") (pin "8") (pinfunction "VS2_8") (pintype "bidirectional"))
      (node (ref "IC6") (pin "1") (pinfunction "VS1_1") (pintype "bidirectional"))
      (node (ref "IC6") (pin "8") (pinfunction "VS2_8") (pintype "bidirectional"))
      (node (ref "IC7") (pin "1") (pinfunction "VS1_1") (pintype "bidirectional"))
      (node (ref "IC7") (pin "8") (pinfunction "VS2_8") (pintype "bidirectional"))
      (node (ref "IC8") (pin "1") (pinfunction "VS1_1") (pintype "bidirectional"))
      (node (ref "IC8") (pin "8") (pinfunction "VS2_8") (pintype "bidirectional"))
      (node (ref "REG1") (pin "G") (pinfunction "IN_G") (pintype "bidirectional"))
    )
    (net (code "62") (name "VCC") (class "Default")
      (node (ref "BEAD_A") (pin "2") (pinfunction "2_2") (pintype "passive"))
      (node (ref "C10") (pin "1") (pinfunction "1_1") (pintype "passive"))
      (node (ref "C37") (pin "1") (pinfunction "1_1") (pintype "passive"))
      (node (ref "C38") (pin "1") (pinfunction "1_1") (pintype "passive"))
      (node (ref "C39") (pin "1") (pinfunction "1_1") (pintype "passive"))
      (node (ref "C41") (pin "1") (pinfunction "1_1") (pintype "passive"))
      (node (ref "C7") (pin "1") (pinfunction "1_1") (pintype "passive"))
      (node (ref "CON5") (pin "2") (pinfunction "P$2_2") (pintype "bidirectional"))
      (node (ref "D2") (pin "C") (pinfunction "C_C") (pintype "passive"))
      (node (ref "IC1") (pin "17") (pinfunction "VCC1_17") (pintype "power_in"))
      (node (ref "IC1") (pin "38") (pinfunction "VCC2_38") (pintype "power_in"))
      (node (ref "IC1") (pin "5") (pinfunction "VCC_5") (pintype "power_in"))
      (node (ref "IC5") (pin "8") (pinfunction "VCC_8") (pintype "bidirectional"))
      (node (ref "R1") (pin "2") (pinfunction "2_2") (pintype "passive"))
      (node (ref "R10") (pin "2") (pinfunction "2_2") (pintype "passive"))
      (node (ref "R11") (pin "2") (pinfunction "2_2") (pintype "passive"))
      (node (ref "R17") (pin "2") (pinfunction "2_2") (pintype "passive"))
      (node (ref "R18") (pin "2") (pinfunction "2_2") (pintype "passive"))
      (node (ref "R2") (pin "2") (pinfunction "2_2") (pintype "passive"))
      (node (ref "R3") (pin "2") (pinfunction "2_2") (pintype "passive"))
      (node (ref "R4") (pin "2") (pinfunction "2_2") (pintype "passive"))
      (node (ref "R5") (pin "2") (pinfunction "2_2") (pintype "passive"))
      (node (ref "R7") (pin "2") (pinfunction "2_2") (pintype "passive"))
      (node (ref "R8") (pin "2") (pinfunction "2_2") (pintype "passive"))
      (node (ref "R9") (pin "2") (pinfunction "2_2") (pintype "passive"))
      (node (ref "REG1") (pin "S") (pinfunction "OUT_S") (pintype "bidirectional"))
      (node (ref "X1") (pin "2") (pinfunction "P$1_2") (pintype "bidirectional"))
    )
    (net (code "63") (name "unconnected-(CON6-Pad1.3)") (class "Default")
      (node (ref "CON6") (pin "1.3") (pinfunction "1.3_1.3") (pintype "bidirectional"))
    )
    (net (code "64") (name "unconnected-(CON6-Pad1.4)") (class "Default")
      (node (ref "CON6") (pin "1.4") (pinfunction "1.4_1.4") (pintype "bidirectional"))
    )
    (net (code "65") (name "unconnected-(CON6-Pad1.5)") (class "Default")
      (node (ref "CON6") (pin "1.5") (pinfunction "1.5_1.5") (pintype "bidirectional"))
    )
    (net (code "66") (name "unconnected-(CON6-Pad1.6)") (class "Default")
      (node (ref "CON6") (pin "1.6") (pinfunction "1.6_1.6") (pintype "bidirectional"))
    )
    (net (code "67") (name "unconnected-(CON6-Pad2.3)") (class "Default")
      (node (ref "CON6") (pin "2.3") (pinfunction "2.3_2.3") (pintype "bidirectional"))
    )
    (net (code "68") (name "unconnected-(CON6-Pad2.4)") (class "Default")
      (node (ref "CON6") (pin "2.4") (pinfunction "2.4_2.4") (pintype "bidirectional"))
    )
    (net (code "69") (name "unconnected-(CON6-Pad2.5)") (class "Default")
      (node (ref "CON6") (pin "2.5") (pinfunction "2.5_2.5") (pintype "bidirectional"))
    )
    (net (code "70") (name "unconnected-(CON6-Pad2.6)") (class "Default")
      (node (ref "CON6") (pin "2.6") (pinfunction "2.6_2.6") (pintype "bidirectional"))
    )
    (net (code "71") (name "unconnected-(IC1-PC0(SCL)-Pad19)") (class "Default")
      (node (ref "IC1") (pin "19") (pinfunction "PC0(SCL)_19") (pintype "bidirectional"))
    )
    (net (code "72") (name "unconnected-(IC1-PC1(SDA)-Pad20)") (class "Default")
      (node (ref "IC1") (pin "20") (pinfunction "PC1(SDA)_20") (pintype "bidirectional"))
    )
    (net (code "73") (name "unconnected-(SW1-2-PadP$2)") (class "Default")
      (node (ref "SW1") (pin "P$2") (pinfunction "2_P$2") (pintype "bidirectional"))
    )
    (net (code "74") (name "{slash}RESET") (class "Default")
      (node (ref "C1") (pin "1") (pinfunction "1_1") (pintype "passive"))
      (node (ref "CON5") (pin "5") (pinfunction "P$5_5") (pintype "bidirectional"))
      (node (ref "D2") (pin "A") (pinfunction "A_A") (pintype "passive"))
      (node (ref "IC1") (pin "4") (pinfunction "RESET_4") (pintype "input"))
      (node (ref "R1") (pin "1") (pinfunction "1_1") (pintype "passive"))
    )
    (net (code "75") (name "{slash}RE_RS485") (class "Default")
      (node (ref "IC1") (pin "22") (pinfunction "(TMS)PC3_22") (pintype "bidirectional"))
      (node (ref "IC5") (pin "2") (pinfunction "/RE_2") (pintype "bidirectional"))
      (node (ref "R5") (pin "1") (pinfunction "1_1") (pintype "passive"))
    )
    (net (code "76") (name "{slash}SS") (class "Default")
      (node (ref "IC1") (pin "44") (pinfunction "(SS)PB4_44") (pintype "bidirectional"))
    )
  )
)
